# 10_SOC_SERDES0_IF.net
KiCad netlist of a schematic drawn in Altium Designer
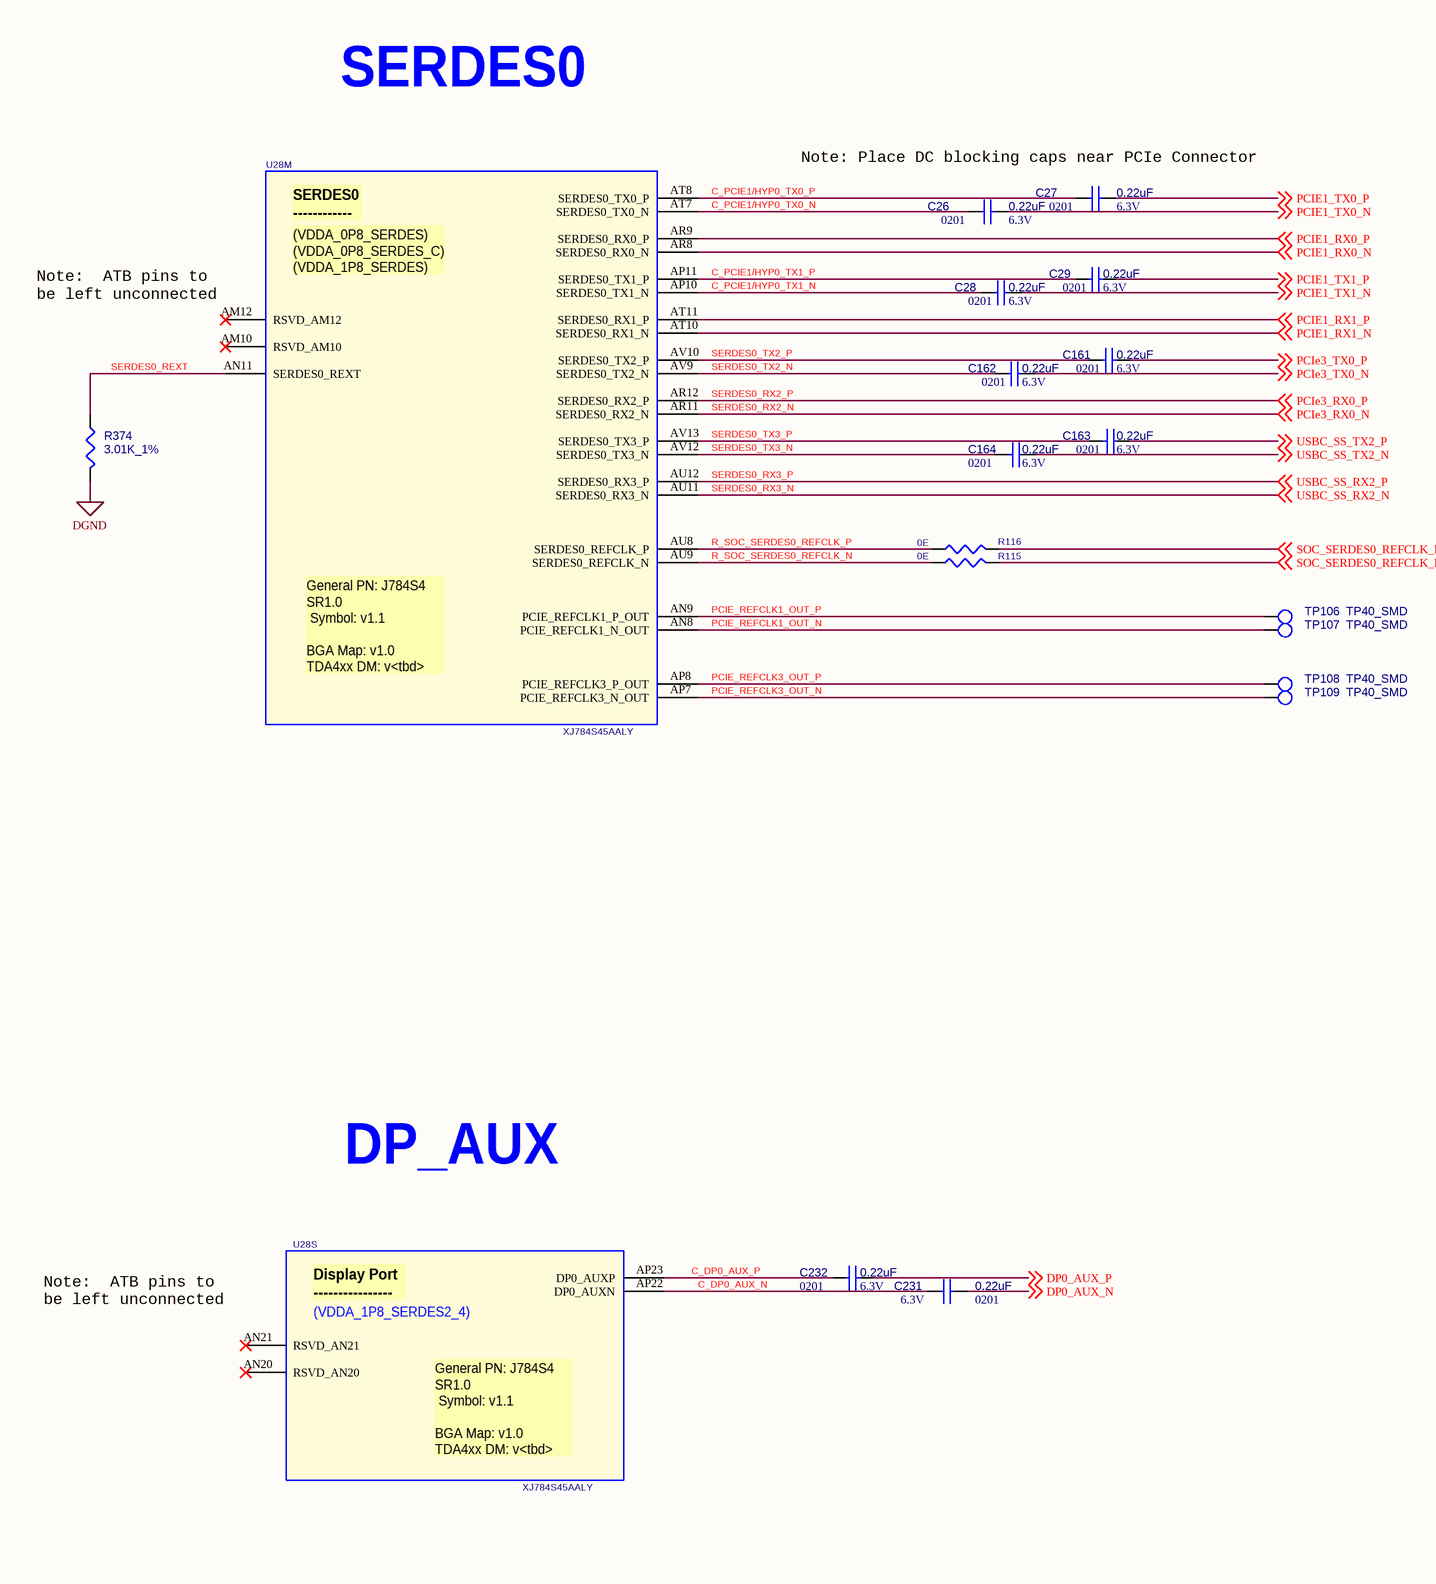
[diagram p0: 10. SOC SERDES0 IF.SchDoc, left]
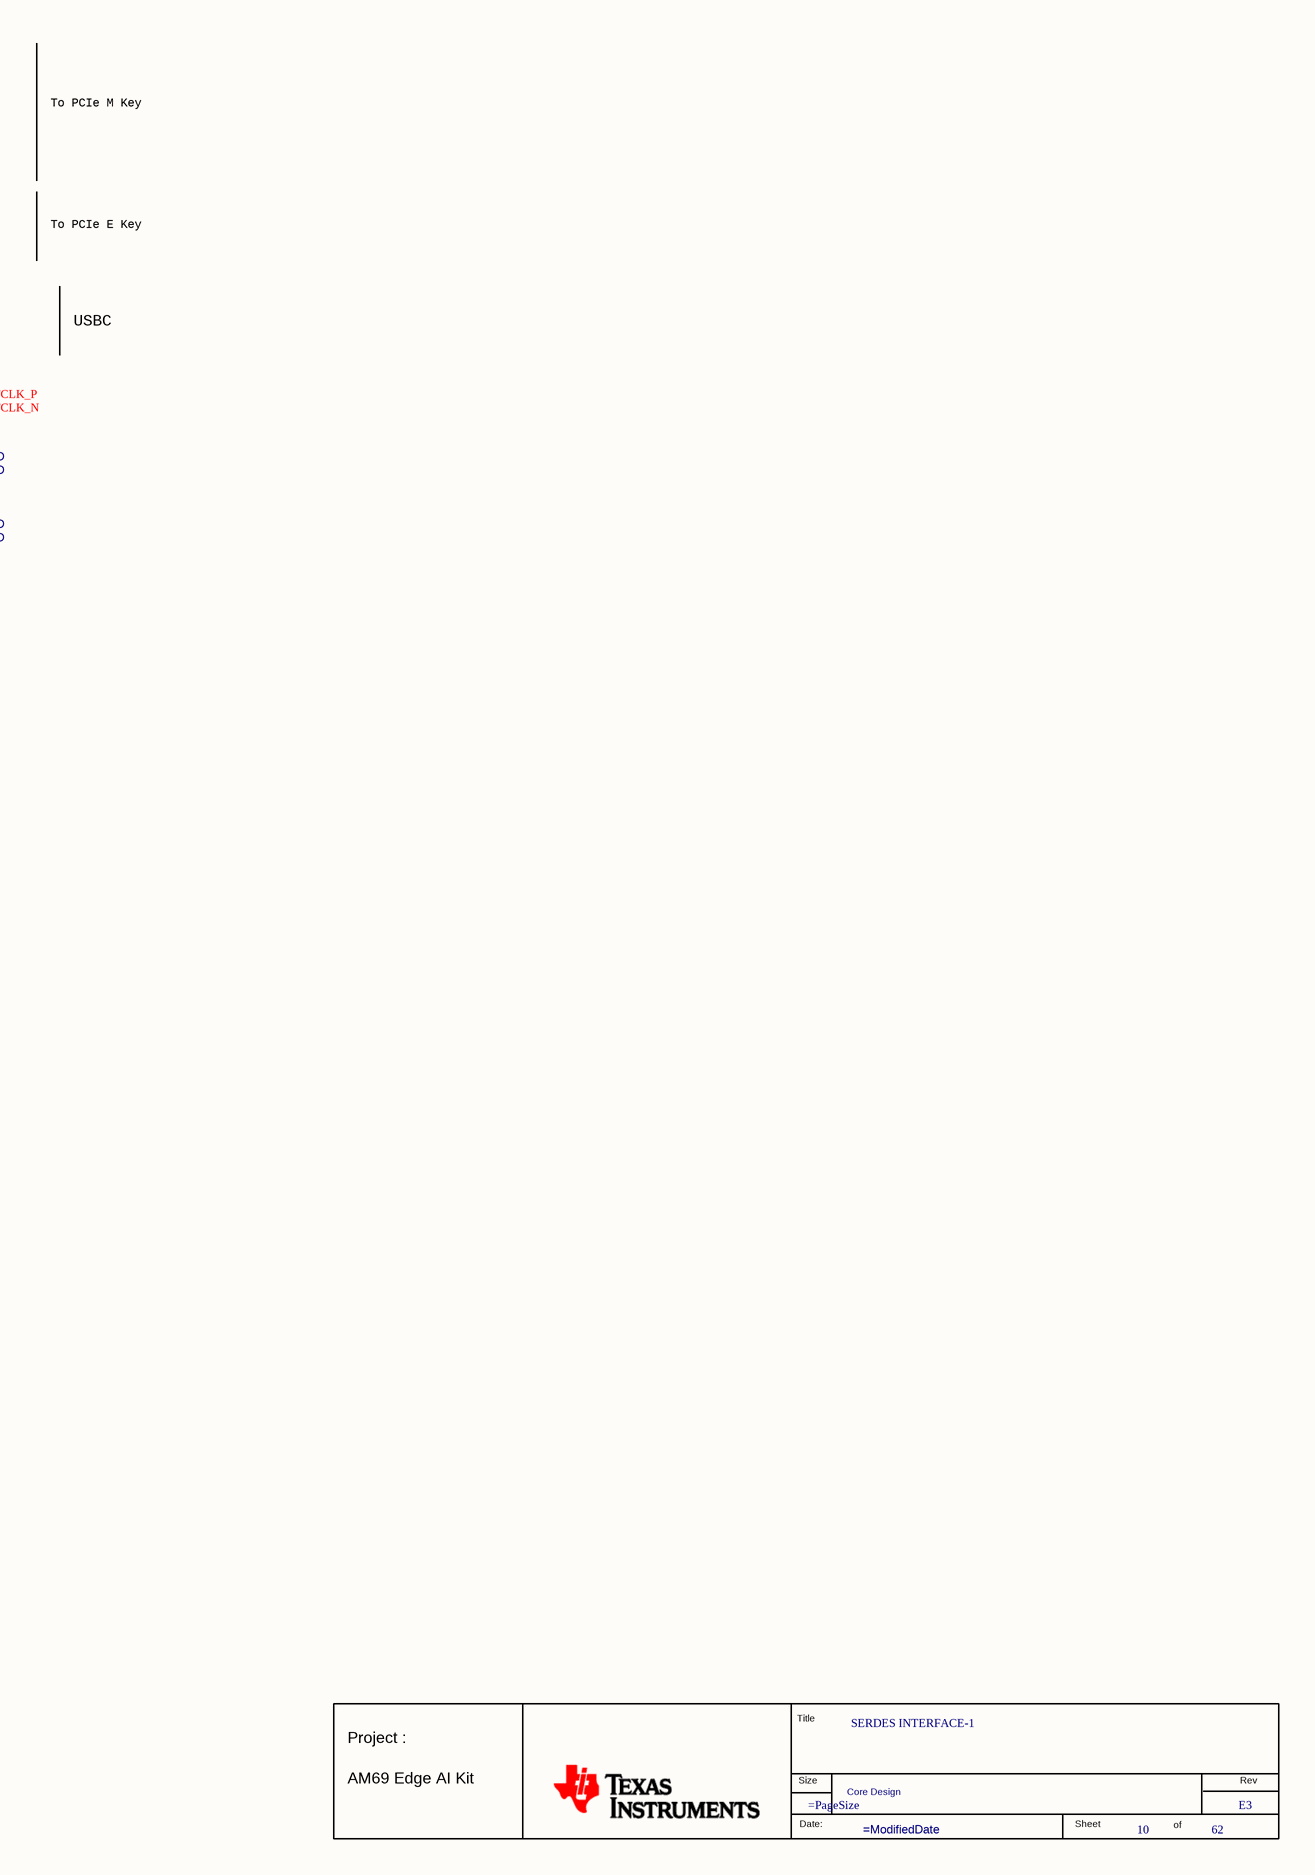
[diagram p1: 10. SOC SERDES0 IF.SchDoc, right]

(export (version "E")
  (design (tool "Eeschema 10.0.6"))
  (components
    (comp (ref "C26")
      (value "0.22uF")
      (footprint "CAP0201_0-5")
      (description "CAP CERAMIC 0.22uF 6.3V 10% X6S AUTO 0201")
      (fields
        (field (name "MANUFACTURER") "MURATA")
        (field (name "DISTRIBUTOR_PART_NUMBER") "490-12230-1-ND")
        (field (name "PACKAGE") "0201")
        (field (name "VOLTAGE") "6.3V")
        (field (name "LIBRARY PATH") "Y~{:}MIS_DATABAS~{E}Librar~{y}ALTIUM_TOO~{L}SCHEMATICS_PART~{S}MS_DISCRETE_Library.schlib")
      )
      (libsource (lib "*") (part "CAP_Dup1"))
    )
    (comp (ref "C27")
      (value "0.22uF")
      (footprint "CAP0201_0-5")
      (description "CAP CERAMIC 0.22uF 6.3V 10% X6S AUTO 0201")
      (fields
        (field (name "MANUFACTURER") "MURATA")
        (field (name "MISTRAL PART NO") "120019020011-R")
        (field (name "VOLTAGE") "6.3V")
        (field (name "PACKAGE") "0201")
        (field (name "LIBRARY PATH") "Y~{:}MIS_DATABAS~{E}Librar~{y}ALTIUM_TOO~{L}SCHEMATICS_PART~{S}MS_DISCRETE_Library.schlib")
      )
      (libsource (lib "*") (part "CAP_Dup1"))
    )
    (comp (ref "C28")
      (value "0.22uF")
      (footprint "CAP0201_0-5")
      (description "CAP CERAMIC 0.22uF 6.3V 10% X6S AUTO 0201")
      (fields
        (field (name "MANUFACTURER") "MURATA")
        (field (name "DISTRIBUTOR_PART_NUMBER") "490-12230-1-ND")
        (field (name "PACKAGE") "0201")
        (field (name "VOLTAGE") "6.3V")
        (field (name "LIBRARY PATH") "Y~{:}MIS_DATABAS~{E}Librar~{y}ALTIUM_TOO~{L}SCHEMATICS_PART~{S}MS_DISCRETE_Library.schlib")
      )
      (libsource (lib "*") (part "CAP_Dup1"))
    )
    (comp (ref "C29")
      (value "0.22uF")
      (footprint "CAP0201_0-5")
      (description "CAP CERAMIC 0.22uF 6.3V 10% X6S AUTO 0201")
      (fields
        (field (name "MANUFACTURER") "MURATA")
        (field (name "DISTRIBUTOR_PART_NUMBER") "490-12230-1-ND")
        (field (name "PACKAGE") "0201")
        (field (name "VOLTAGE") "6.3V")
        (field (name "LIBRARY PATH") "Y~{:}MIS_DATABAS~{E}Librar~{y}ALTIUM_TOO~{L}SCHEMATICS_PART~{S}MS_DISCRETE_Library.schlib")
      )
      (libsource (lib "*") (part "CAP_Dup1"))
    )
    (comp (ref "C161")
      (value "0.22uF")
      (footprint "CAP0201_0-5")
      (description "CAP CERAMIC 0.22uF 6.3V 10% X6S AUTO 0201")
      (fields
        (field (name "MANUFACTURER") "MURATA")
        (field (name "MISTRAL PART NO") "120019020011-R")
        (field (name "VOLTAGE") "6.3V")
        (field (name "PACKAGE") "0201")
        (field (name "LIBRARY PATH") "Y~{:}MIS_DATABAS~{E}Librar~{y}ALTIUM_TOO~{L}SCHEMATICS_PART~{S}MS_DISCRETE_Library.schlib")
      )
      (libsource (lib "*") (part "CAP_Dup1"))
    )
    (comp (ref "C162")
      (value "0.22uF")
      (footprint "CAP0201_0-5")
      (description "CAP CERAMIC 0.22uF 6.3V 10% X6S AUTO 0201")
      (fields
        (field (name "MANUFACTURER") "MURATA")
        (field (name "MISTRAL PART NO") "120019020011-R")
        (field (name "VOLTAGE") "6.3V")
        (field (name "PACKAGE") "0201")
        (field (name "LIBRARY PATH") "Y~{:}MIS_DATABAS~{E}Librar~{y}ALTIUM_TOO~{L}SCHEMATICS_PART~{S}MS_DISCRETE_Library.schlib")
      )
      (libsource (lib "*") (part "CAP_Dup1"))
    )
    (comp (ref "C163")
      (value "0.22uF")
      (footprint "CAP0201_0-5")
      (description "CAP CERAMIC 0.22uF 6.3V 10% X6S AUTO 0201")
      (fields
        (field (name "DISTRIBUTOR_PART_NUMBER") "490-12230-1-ND")
        (field (name "PACKAGE") "0201")
        (field (name "VOLTAGE") "6.3V")
        (field (name "TOLERANCE") "10%")
        (field (name "LIBRARY PATH") "Y~{:}MIS_DATABAS~{E}Librar~{y}ALTIUM_TOO~{L}SCHEMATICS_PART~{S}MS_DISCRETE_Library.schlib")
      )
      (libsource (lib "*") (part "CAP_Dup1"))
    )
    (comp (ref "C164")
      (value "0.22uF")
      (footprint "CAP0201_0-5")
      (description "CAP CERAMIC 0.22uF 6.3V 10% X6S AUTO 0201")
      (fields
        (field (name "MISTRAL PART NO") "120019020011-R")
        (field (name "MFR_PART_NUMBER") "GRT033C80J224KE01D")
        (field (name "VOLTAGE") "6.3V")
        (field (name "PACKAGE") "0201")
        (field (name "LIBRARY PATH") "Y~{:}MIS_DATABAS~{E}Librar~{y}ALTIUM_TOO~{L}SCHEMATICS_PART~{S}MS_DISCRETE_Library.schlib")
      )
      (libsource (lib "*") (part "CAP_Dup1"))
    )
    (comp (ref "C231")
      (value "0.22uF")
      (footprint "CAP0201_0-5")
      (description "CAP CERAMIC 0.22uF 6.3V 10% X6S AUTO 0201")
      (fields
        (field (name "MISTRAL PART NO") "120019020011-R")
        (field (name "MFR_PART_NUMBER") "GRT033C80J224KE01D")
        (field (name "VOLTAGE") "6.3V")
        (field (name "PACKAGE") "0201")
        (field (name "LIBRARY PATH") "Y~{:}MIS_DATABAS~{E}Librar~{y}ALTIUM_TOO~{L}SCHEMATICS_PART~{S}MS_DISCRETE_Library.schlib")
      )
      (libsource (lib "*") (part "CAP_Dup1"))
    )
    (comp (ref "C232")
      (value "0.22uF")
      (footprint "CAP0201_0-5")
      (description "CAP CERAMIC 0.22uF 6.3V 10% X6S AUTO 0201")
      (fields
        (field (name "DISTRIBUTOR_PART_NUMBER") "490-12230-1-ND")
        (field (name "PACKAGE") "0201")
        (field (name "VOLTAGE") "6.3V")
        (field (name "TOLERANCE") "10%")
        (field (name "LIBRARY PATH") "Y~{:}MIS_DATABAS~{E}Librar~{y}ALTIUM_TOO~{L}SCHEMATICS_PART~{S}MS_DISCRETE_Library.schlib")
      )
      (libsource (lib "*") (part "CAP_Dup1"))
    )
    (comp (ref "R115")
      (value "0E")
      (footprint "RES0201_0-5")
      (description "RES 0E 1/20W 5% 0201")
      (fields
        (field (name "MANUFACTURER") "YAGEO AMERICA")
        (field (name "MISTRAL PART NO") "110010070067-R")
        (field (name "LIBRARY PATH") "Y~{:}MIS_DATABAS~{E}Librar~{y}ALTIUM_TOO~{L}SCHEMATICS_PART~{S}MS_DISCRETE_Library.schlib")
      )
      (libsource (lib "*") (part "RESISTOR"))
    )
    (comp (ref "R116")
      (value "0E")
      (footprint "RES0201_0-5")
      (description "RES 0E 1/20W 5% 0201")
      (fields
        (field (name "MANUFACTURER") "YAGEO AMERICA")
        (field (name "DISTRIBUTOR_PART_NUMBER") "311-0.0NCT-ND")
        (field (name "LIBRARY PATH") "Y~{:}MIS_DATABAS~{E}Librar~{y}ALTIUM_TOO~{L}SCHEMATICS_PART~{S}MS_DISCRETE_Library.schlib")
      )
      (libsource (lib "*") (part "RESISTOR"))
    )
    (comp (ref "R374")
      (value "3.01K_1%")
      (footprint "RES0201_0-5")
      (description "RES 3.01K 1/20W 1% 0201")
      (fields
        (field (name "MANUFACTURER") "PANASONIC-ECG")
        (field (name "DISTRIBUTOR_PART_NUMBER") "P122916CT-ND")
        (field (name "LIBRARY PATH") "Y~{:}MIS_DATABAS~{E}Librar~{y}ALTIUM_TOO~{L}SCHEMATICS_PART~{S}MS_DISCRETE_Library.schlib")
      )
      (libsource (lib "*") (part "RESISTOR_Dup2"))
    )
    (comp (ref "TP106")
      (value "TP40_SMD")
      (footprint "TP40_SMD")
      (description "TESTPOINT CIR 40 SMD")
      (fields
        (field (name "DISTRIBUTOR_PART_NUMBER") "NA")
        (field (name "MISTRAL PART NO") "130009030933")
        (field (name "LIBRARY PATH") "Y~{:}MIS_DATABAS~{E}Librar~{y}ALTIUM_TOO~{L}SCHEMATICS_PART~{S}MS_DISCRETE_Library.schlib")
      )
      (libsource (lib "*") (part "TESTPOINT_Dup1"))
    )
    (comp (ref "TP107")
      (value "TP40_SMD")
      (footprint "TP40_SMD")
      (description "TESTPOINT CIR 40 SMD")
      (fields
        (field (name "DISTRIBUTOR_PART_NUMBER") "NA")
        (field (name "MISTRAL PART NO") "130009030933")
        (field (name "LIBRARY PATH") "Y~{:}MIS_DATABAS~{E}Librar~{y}ALTIUM_TOO~{L}SCHEMATICS_PART~{S}MS_DISCRETE_Library.schlib")
      )
      (libsource (lib "*") (part "TESTPOINT_Dup1"))
    )
    (comp (ref "TP108")
      (value "TP40_SMD")
      (footprint "TP40_SMD")
      (description "TESTPOINT CIR 40 SMD")
      (fields
        (field (name "DISTRIBUTOR_PART_NUMBER") "NA")
        (field (name "MISTRAL PART NO") "130009030933")
        (field (name "LIBRARY PATH") "Y~{:}MIS_DATABAS~{E}Librar~{y}ALTIUM_TOO~{L}SCHEMATICS_PART~{S}MS_DISCRETE_Library.schlib")
      )
      (libsource (lib "*") (part "TESTPOINT_Dup1"))
    )
    (comp (ref "TP109")
      (value "TP40_SMD")
      (footprint "TP40_SMD")
      (description "TESTPOINT CIR 40 SMD")
      (fields
        (field (name "DISTRIBUTOR_PART_NUMBER") "NA")
        (field (name "MISTRAL PART NO") "130009030933")
        (field (name "LIBRARY PATH") "Y~{:}MIS_DATABAS~{E}Librar~{y}ALTIUM_TOO~{L}SCHEMATICS_PART~{S}MS_DISCRETE_Library.schlib")
      )
      (libsource (lib "*") (part "TESTPOINT_Dup1"))
    )
    (comp (ref "U28")
      (value "XJ784S45AALY")
      (footprint "BGA1414_31-49_1230X1230_2-7")
      (description "IC AM69 SoC EVM MICROPROCESSOR BGA1414")
      (fields
        (field (name "DISTRIBUTOR_PART_NUMBER") "NA")
        (field (name "MISTRAL PART NO") "141230020002")
        (field (name "MANUFACTURER") "TEXAS INSTRUMENTS")
        (field (name "LIBRARY PATH") "Y~{:}MIS_DATABAS~{E}Librar~{y}ALTIUM_TOO~{L}SCHEMATICS_PART~{S}MS_MICROPROCESSOR_Library.schlib")
      )
      (libsource (lib "*") (part "J7AHPSoC-EVM_BGA1414"))
    )
  )
  (nets
    (net (code "1") (name "/C_DP0_AUX_N") (class "Default")
      (node (ref "C231") (pin "1") (pinfunction "1_1") (pintype "passive"))
      (node (ref "U28") (pin "AP22") (pinfunction "DP0_AUXN_AP22") (pintype "passive"))
    )
    (net (code "2") (name "/C_DP0_AUX_P") (class "Default")
      (node (ref "C232") (pin "1") (pinfunction "1_1") (pintype "passive"))
      (node (ref "U28") (pin "AP23") (pinfunction "DP0_AUXP_AP23") (pintype "passive"))
    )
    (net (code "3") (name "/C_PCIE1{slash}HYP0_TX0_N") (class "Default")
      (node (ref "C26") (pin "1") (pinfunction "1_1") (pintype "passive"))
      (node (ref "U28") (pin "AT7") (pinfunction "SERDES0_TX0_N_AT7") (pintype "passive"))
    )
    (net (code "4") (name "/C_PCIE1{slash}HYP0_TX0_P") (class "Default")
      (node (ref "C27") (pin "1") (pinfunction "1_1") (pintype "passive"))
      (node (ref "U28") (pin "AT8") (pinfunction "SERDES0_TX0_P_AT8") (pintype "passive"))
    )
    (net (code "5") (name "/C_PCIE1{slash}HYP0_TX1_N") (class "Default")
      (node (ref "C28") (pin "1") (pinfunction "1_1") (pintype "passive"))
      (node (ref "U28") (pin "AP10") (pinfunction "SERDES0_TX1_N_AP10") (pintype "passive"))
    )
    (net (code "6") (name "/C_PCIE1{slash}HYP0_TX1_P") (class "Default")
      (node (ref "C29") (pin "1") (pinfunction "1_1") (pintype "passive"))
      (node (ref "U28") (pin "AP11") (pinfunction "SERDES0_TX1_P_AP11") (pintype "passive"))
    )
    (net (code "7") (name "/PCIE_REFCLK1_OUT_N") (class "Default")
      (node (ref "TP107") (pin "1") (pinfunction "TP_1") (pintype "passive"))
      (node (ref "U28") (pin "AN8") (pinfunction "PCIE_REFCLK1_N_OUT_AN8") (pintype "passive"))
    )
    (net (code "8") (name "/PCIE_REFCLK1_OUT_P") (class "Default")
      (node (ref "TP106") (pin "1") (pinfunction "TP_1") (pintype "passive"))
      (node (ref "U28") (pin "AN9") (pinfunction "PCIE_REFCLK1_P_OUT_AN9") (pintype "passive"))
    )
    (net (code "9") (name "/PCIE_REFCLK3_OUT_N") (class "Default")
      (node (ref "TP109") (pin "1") (pinfunction "TP_1") (pintype "passive"))
      (node (ref "U28") (pin "AP7") (pinfunction "PCIE_REFCLK3_N_OUT_AP7") (pintype "passive"))
    )
    (net (code "10") (name "/PCIE_REFCLK3_OUT_P") (class "Default")
      (node (ref "TP108") (pin "1") (pinfunction "TP_1") (pintype "passive"))
      (node (ref "U28") (pin "AP8") (pinfunction "PCIE_REFCLK3_P_OUT_AP8") (pintype "passive"))
    )
    (net (code "11") (name "/R_SOC_SERDES0_REFCLK_N") (class "Default")
      (node (ref "R115") (pin "2") (pinfunction "2_2") (pintype "passive"))
      (node (ref "U28") (pin "AU9") (pinfunction "SERDES0_REFCLK_N_AU9") (pintype "passive"))
    )
    (net (code "12") (name "/R_SOC_SERDES0_REFCLK_P") (class "Default")
      (node (ref "R116") (pin "2") (pinfunction "2_2") (pintype "passive"))
      (node (ref "U28") (pin "AU8") (pinfunction "SERDES0_REFCLK_P_AU8") (pintype "passive"))
    )
    (net (code "13") (name "/SERDES0_REXT") (class "Default")
      (node (ref "R374") (pin "1") (pinfunction "1_1") (pintype "passive"))
      (node (ref "U28") (pin "AN11") (pinfunction "SERDES0_REXT_AN11") (pintype "passive"))
    )
    (net (code "14") (name "/SERDES0_TX2_N") (class "Default")
      (node (ref "C162") (pin "1") (pinfunction "1_1") (pintype "passive"))
      (node (ref "U28") (pin "AV9") (pinfunction "SERDES0_TX2_N_AV9") (pintype "passive"))
    )
    (net (code "15") (name "/SERDES0_TX2_P") (class "Default")
      (node (ref "C161") (pin "1") (pinfunction "1_1") (pintype "passive"))
      (node (ref "U28") (pin "AV10") (pinfunction "SERDES0_TX2_P_AV10") (pintype "passive"))
    )
    (net (code "16") (name "/SERDES0_TX3_N") (class "Default")
      (node (ref "C164") (pin "2") (pinfunction "2_2") (pintype "passive"))
      (node (ref "U28") (pin "AV12") (pinfunction "SERDES0_TX3_N_AV12") (pintype "passive"))
    )
    (net (code "17") (name "/SERDES0_TX3_P") (class "Default")
      (node (ref "C163") (pin "2") (pinfunction "2_2") (pintype "passive"))
      (node (ref "U28") (pin "AV13") (pinfunction "SERDES0_TX3_P_AV13") (pintype "passive"))
    )
    (net (code "18") (name "DGND") (class "Default")
      (node (ref "R374") (pin "2") (pinfunction "2_2") (pintype "passive"))
    )
    (net (code "19") (name "DP0_AUX_N") (class "Default")
      (node (ref "C231") (pin "2") (pinfunction "2_2") (pintype "passive"))
    )
    (net (code "20") (name "DP0_AUX_P") (class "Default")
      (node (ref "C232") (pin "2") (pinfunction "2_2") (pintype "passive"))
    )
    (net (code "21") (name "PCIE1_RX0_N") (class "Default")
      (node (ref "U28") (pin "AR8") (pinfunction "SERDES0_RX0_N_AR8") (pintype "passive"))
    )
    (net (code "22") (name "PCIE1_RX0_P") (class "Default")
      (node (ref "U28") (pin "AR9") (pinfunction "SERDES0_RX0_P_AR9") (pintype "passive"))
    )
    (net (code "23") (name "PCIE1_RX1_N") (class "Default")
      (node (ref "U28") (pin "AT10") (pinfunction "SERDES0_RX1_N_AT10") (pintype "passive"))
    )
    (net (code "24") (name "PCIE1_RX1_P") (class "Default")
      (node (ref "U28") (pin "AT11") (pinfunction "SERDES0_RX1_P_AT11") (pintype "passive"))
    )
    (net (code "25") (name "PCIE1_TX0_N") (class "Default")
      (node (ref "C26") (pin "2") (pinfunction "2_2") (pintype "passive"))
    )
    (net (code "26") (name "PCIE1_TX0_P") (class "Default")
      (node (ref "C27") (pin "2") (pinfunction "2_2") (pintype "passive"))
    )
    (net (code "27") (name "PCIE1_TX1_N") (class "Default")
      (node (ref "C28") (pin "2") (pinfunction "2_2") (pintype "passive"))
    )
    (net (code "28") (name "PCIE1_TX1_P") (class "Default")
      (node (ref "C29") (pin "2") (pinfunction "2_2") (pintype "passive"))
    )
    (net (code "29") (name "PCIe3_RX0_N") (class "Default")
      (node (ref "U28") (pin "AR11") (pinfunction "SERDES0_RX2_N_AR11") (pintype "passive"))
    )
    (net (code "30") (name "PCIe3_RX0_P") (class "Default")
      (node (ref "U28") (pin "AR12") (pinfunction "SERDES0_RX2_P_AR12") (pintype "passive"))
    )
    (net (code "31") (name "PCIe3_TX0_N") (class "Default")
      (node (ref "C162") (pin "2") (pinfunction "2_2") (pintype "passive"))
    )
    (net (code "32") (name "PCIe3_TX0_P") (class "Default")
      (node (ref "C161") (pin "2") (pinfunction "2_2") (pintype "passive"))
    )
    (net (code "33") (name "SOC_SERDES0_REFCLK_N") (class "Default")
      (node (ref "R115") (pin "1") (pinfunction "1_1") (pintype "passive"))
    )
    (net (code "34") (name "SOC_SERDES0_REFCLK_P") (class "Default")
      (node (ref "R116") (pin "1") (pinfunction "1_1") (pintype "passive"))
    )
    (net (code "35") (name "USBC_SS_RX2_N") (class "Default")
      (node (ref "U28") (pin "AU11") (pinfunction "SERDES0_RX3_N_AU11") (pintype "passive"))
    )
    (net (code "36") (name "USBC_SS_RX2_P") (class "Default")
      (node (ref "U28") (pin "AU12") (pinfunction "SERDES0_RX3_P_AU12") (pintype "passive"))
    )
    (net (code "37") (name "USBC_SS_TX2_N") (class "Default")
      (node (ref "C164") (pin "1") (pinfunction "1_1") (pintype "passive"))
    )
    (net (code "38") (name "USBC_SS_TX2_P") (class "Default")
      (node (ref "C163") (pin "1") (pinfunction "1_1") (pintype "passive"))
    )
    (net (code "39") (name "unconnected-(U28M-RSVD_AM10-PadAM10)") (class "Default")
      (node (ref "U28") (pin "AM10") (pinfunction "RSVD_AM10_AM10") (pintype "passive+no_connect"))
    )
    (net (code "40") (name "unconnected-(U28M-RSVD_AM12-PadAM12)") (class "Default")
      (node (ref "U28") (pin "AM12") (pinfunction "RSVD_AM12_AM12") (pintype "passive+no_connect"))
    )
    (net (code "41") (name "unconnected-(U28S-RSVD_AN20-PadAN20)") (class "Default")
      (node (ref "U28") (pin "AN20") (pinfunction "RSVD_AN20_AN20") (pintype "passive+no_connect"))
    )
    (net (code "42") (name "unconnected-(U28S-RSVD_AN21-PadAN21)") (class "Default")
      (node (ref "U28") (pin "AN21") (pinfunction "RSVD_AN21_AN21") (pintype "passive+no_connect"))
    )
  )
)
